# Conditioning.net
KiCad netlist of a schematic drawn in Altium Designer
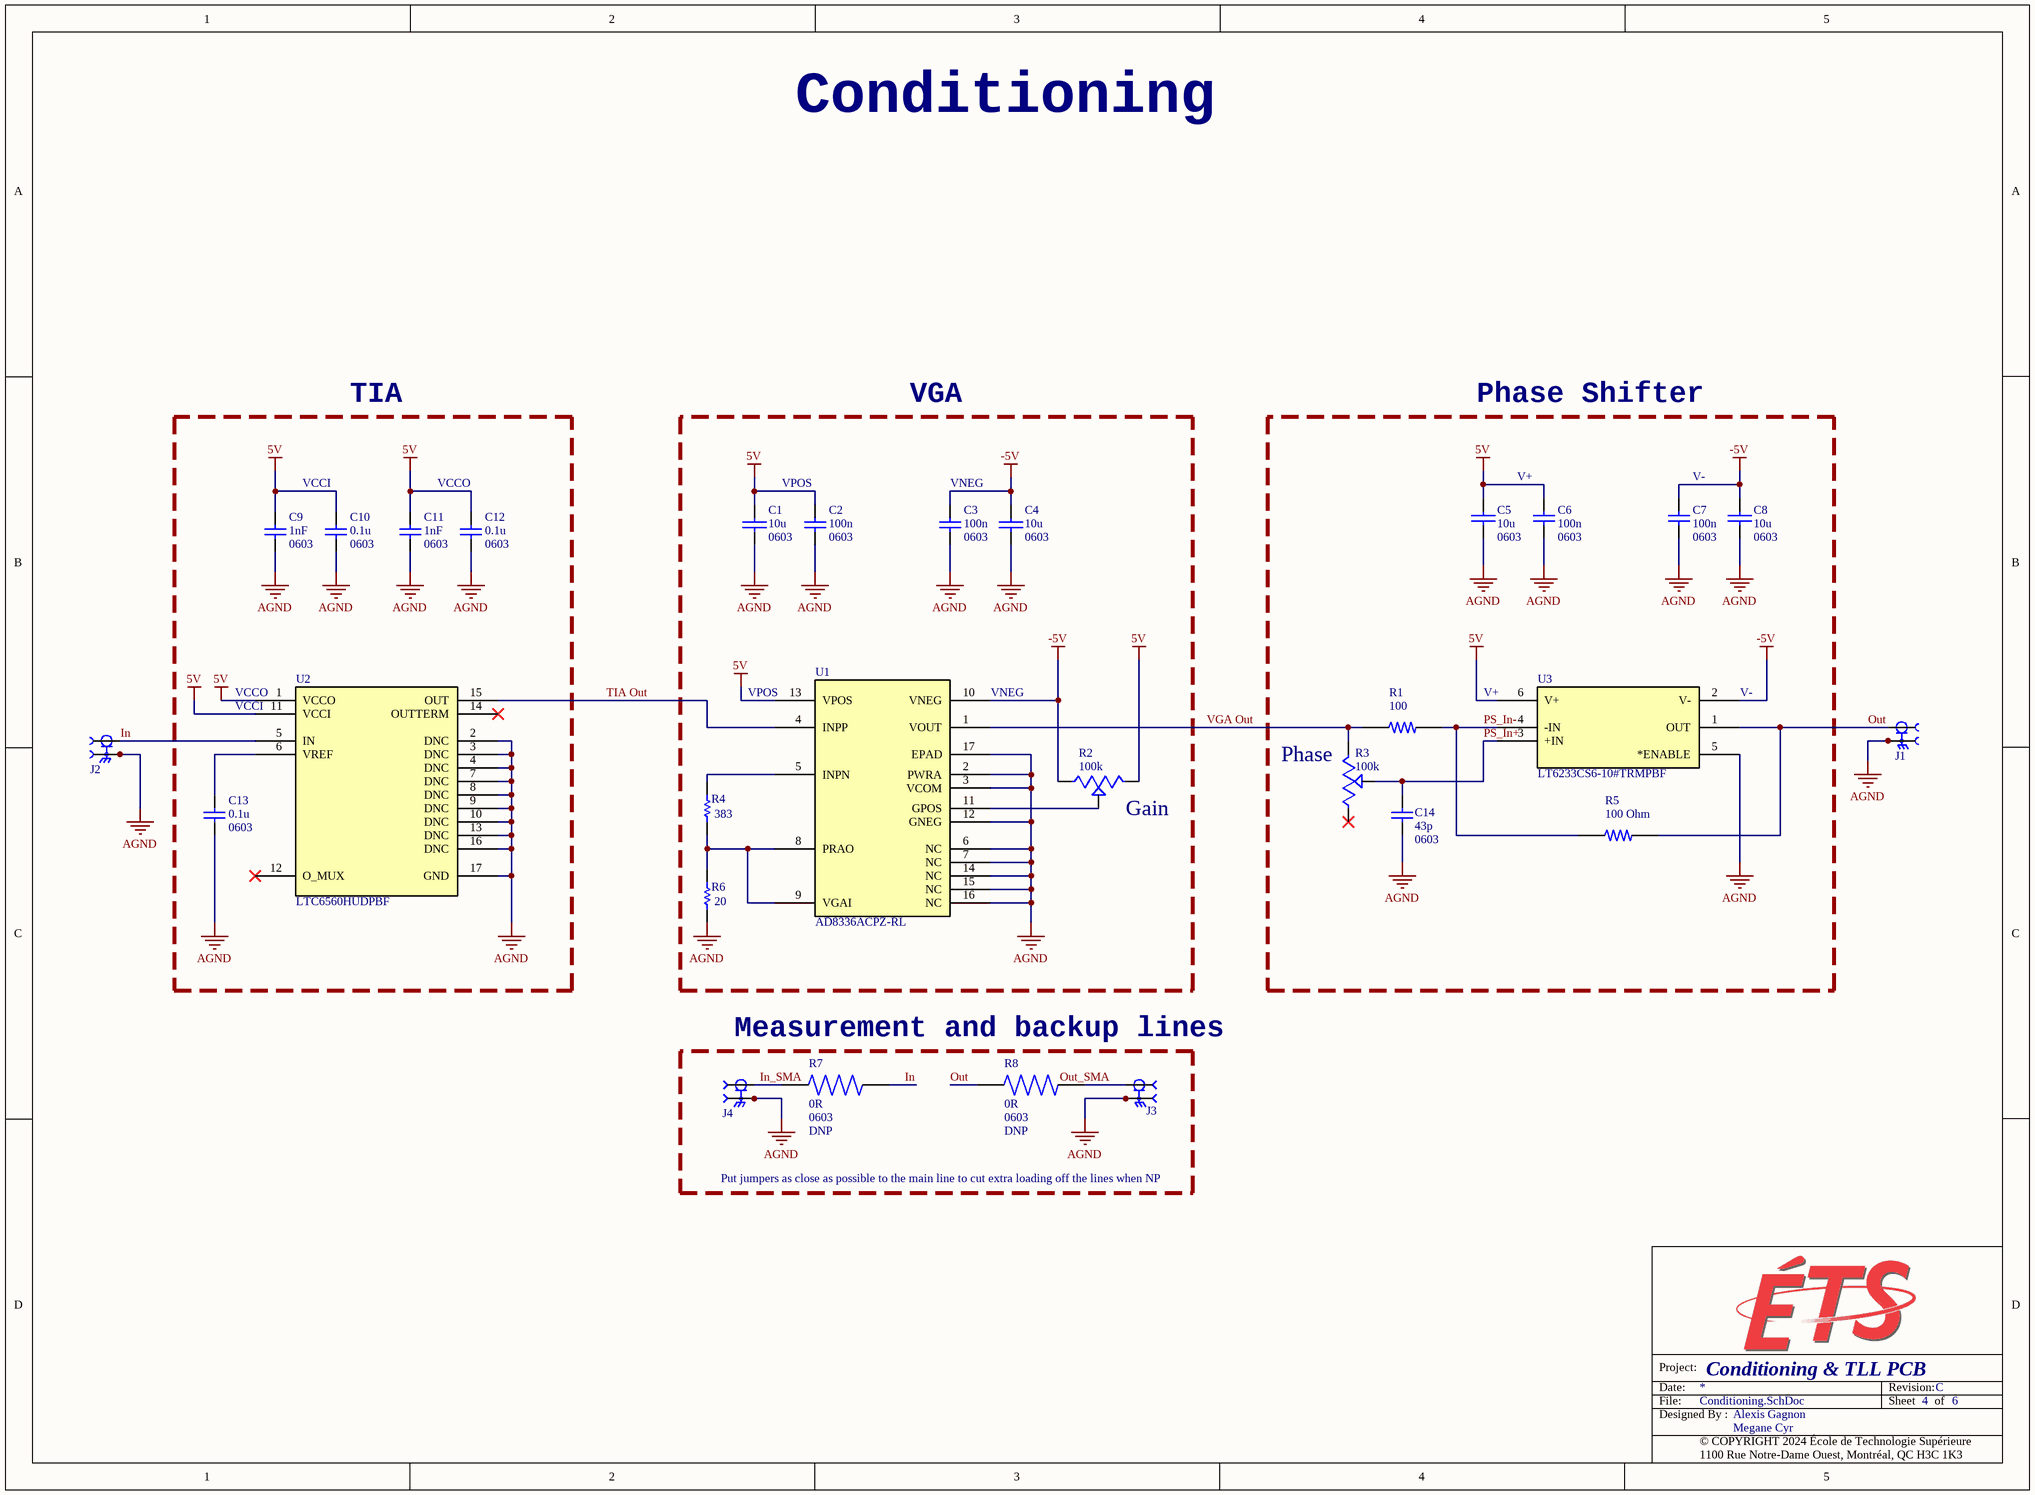
[diagram p0: Conditioning.SchDoc]

(export (version "E")
  (design (tool "Eeschema 10.0.6"))
  (components
    (comp (ref "C1")
      (value "10u")
      (footprint "C0603-V2")
      (description "CAP CER 10UF 10V X7R 0603")
      (fields
        (field (name "MANUFACTURER") "Murata")
        (field (name "MANUFACTURER PART NUMBER") "GRM188Z71A106KA73J")
        (field (name "PACKAGE") "0603")
      )
      (libsource (lib "ETS_Library") (part "GRM188Z71A106KA73J"))
    )
    (comp (ref "C2")
      (value "100n")
      (footprint "C0603-V2")
      (description "CAP CER 0.1UF 50V X7R 0603")
      (fields
        (field (name "MANUFACTURER") "Samsung")
        (field (name "MANUFACTURER PART NUMBER") "CL10B104KB8NNWC")
        (field (name "PACKAGE") "0603")
      )
      (libsource (lib "ETS_Library") (part "CL10B104KB8NNWC"))
    )
    (comp (ref "C3")
      (value "100n")
      (footprint "C0603-V2")
      (description "CAP CER 0.1UF 50V X7R 0603")
      (fields
        (field (name "MANUFACTURER") "Samsung")
        (field (name "MANUFACTURER PART NUMBER") "CL10B104KB8NNWC")
        (field (name "PACKAGE") "0603")
      )
      (libsource (lib "ETS_Library") (part "CL10B104KB8NNWC"))
    )
    (comp (ref "C4")
      (value "10u")
      (footprint "C0603-V2")
      (description "CAP CER 10UF 10V X7R 0603")
      (fields
        (field (name "MANUFACTURER") "Murata")
        (field (name "MANUFACTURER PART NUMBER") "GRM188Z71A106KA73J")
        (field (name "PACKAGE") "0603")
      )
      (libsource (lib "ETS_Library") (part "GRM188Z71A106KA73J"))
    )
    (comp (ref "C5")
      (value "10u")
      (footprint "C0603-V2")
      (description "CAP CER 10UF 10V X7R 0603")
      (fields
        (field (name "MANUFACTURER") "Murata")
        (field (name "MANUFACTURER PART NUMBER") "GRM188Z71A106KA73J")
        (field (name "PACKAGE") "0603")
      )
      (libsource (lib "ETS_Library") (part "GRM188Z71A106KA73J"))
    )
    (comp (ref "C6")
      (value "100n")
      (footprint "C0603-V2")
      (description "CAP CER 0.1UF 50V X7R 0603")
      (fields
        (field (name "MANUFACTURER") "Samsung")
        (field (name "MANUFACTURER PART NUMBER") "CL10B104KB8NNWC")
        (field (name "PACKAGE") "0603")
      )
      (libsource (lib "ETS_Library") (part "CL10B104KB8NNWC"))
    )
    (comp (ref "C7")
      (value "100n")
      (footprint "C0603-V2")
      (description "CAP CER 0.1UF 50V X7R 0603")
      (fields
        (field (name "MANUFACTURER") "Samsung")
        (field (name "MANUFACTURER PART NUMBER") "CL10B104KB8NNWC")
        (field (name "PACKAGE") "0603")
      )
      (libsource (lib "ETS_Library") (part "CL10B104KB8NNWC"))
    )
    (comp (ref "C8")
      (value "10u")
      (footprint "C0603-V2")
      (description "CAP CER 10UF 10V X7R 0603")
      (fields
        (field (name "MANUFACTURER") "Murata")
        (field (name "MANUFACTURER PART NUMBER") "GRM188Z71A106KA73J")
        (field (name "PACKAGE") "0603")
      )
      (libsource (lib "ETS_Library") (part "GRM188Z71A106KA73J"))
    )
    (comp (ref "C9")
      (value "1nF")
      (footprint "C0603-V2")
      (description "CAP CER 1000PF 50V X7R 0603")
      (fields
        (field (name "MANUFACTURER") "Samsung")
        (field (name "MANUFACTURER PART NUMBER") "CL10B102KB8NNNC")
        (field (name "PACKAGE") "0603")
      )
      (libsource (lib "ETS_Library") (part "CL10B102KB8NNNC"))
    )
    (comp (ref "C10")
      (value "0.1u")
      (footprint "C0603-V2")
      (description "CAP CER 0.1UF 50V X7R 0603")
      (fields
        (field (name "MANUFACTURER_PART_NUMBER") "CL10B104KB8NNNC")
        (field (name "PACKAGE") "0603")
        (field (name "COPYRIGHT") "Copyright (C) 2025 Ultra Librarian. All rights reserved.")
      )
      (libsource (lib "ETS_Library") (part "CL10B104KB8NNNC_1"))
    )
    (comp (ref "C11")
      (value "1nF")
      (footprint "C0603-V2")
      (description "CAP CER 1000PF 50V X7R 0603")
      (fields
        (field (name "MANUFACTURER") "Samsung")
        (field (name "MANUFACTURER PART NUMBER") "CL10B102KB8NNNC")
        (field (name "PACKAGE") "0603")
      )
      (libsource (lib "ETS_Library") (part "CL10B102KB8NNNC"))
    )
    (comp (ref "C12")
      (value "0.1u")
      (footprint "C0603-V2")
      (description "CAP CER 0.1UF 50V X7R 0603")
      (fields
        (field (name "MANUFACTURER_PART_NUMBER") "CL10B104KB8NNNC")
        (field (name "PACKAGE") "0603")
        (field (name "COPYRIGHT") "Copyright (C) 2025 Ultra Librarian. All rights reserved.")
      )
      (libsource (lib "ETS_Library") (part "CL10B104KB8NNNC_1"))
    )
    (comp (ref "C13")
      (value "0.1u")
      (footprint "CAP_CL10_SAM")
      (description "CAP CER 0.1UF 50V X7R 0603")
      (fields
        (field (name "MANUFACTURER_PART_NUMBER") "CL10B104KB8NNNC")
        (field (name "PACKAGE") "0603")
        (field (name "COPYRIGHT") "Copyright (C) 2025 Ultra Librarian. All rights reserved.")
      )
      (libsource (lib "ETS_Library") (part "CL10B104KB8NNNC_1"))
    )
    (comp (ref "C14")
      (value "43p")
      (footprint "CAPC1608X90")
      (description "CAP CER 43PF 50V C0G/NPO 0603")
      (fields (field (name "MP") "CC0603JRNPO9BN430") (field (name "PACKAGE") "0603"))
      (libsource (lib "ETS_Library") (part "CC0603JRNPO9BN430"))
    )
    (comp (ref "J1")
      (value "CONSMA001-G")
      (footprint "LINX_CONSMA001-G")
      (description "CONN SMA RCPT STR 50 OHM PCB")
      (libsource (lib "") (part "CONSMA001-G_1"))
    )
    (comp (ref "J2")
      (value "CONSMA001-G")
      (footprint "LINX_CONSMA001-G")
      (description "CONN SMA RCPT STR 50 OHM PCB")
      (libsource (lib "ETS_Library") (part "CONSMA001-G"))
    )
    (comp (ref "J3")
      (value "EMPCB.SMAFSTJ.B.HT")
      (footprint "SMA Connector")
      (description "SMA Connector Jack, Female Socket 50Ohm Board Edge, End Launch Solder")
      (fields (field (name "MF") "Taoglas Limited"))
      (libsource (lib "ELE682") (part "SMA Connector"))
    )
    (comp (ref "J4")
      (value "EMPCB.SMAFSTJ.B.HT")
      (footprint "SMA Connector")
      (description "SMA Connector Jack, Female Socket 50Ohm Board Edge, End Launch Solder")
      (fields (field (name "MF") "Taoglas Limited"))
      (libsource (lib "ELE682") (part "SMA Connector"))
    )
    (comp (ref "R1")
      (value "100")
      (footprint "RESC1607X60N")
      (description "RES SMT 100R 1% 0603 T/R PICK#92931")
      (fields (field (name "MP") "RC0603FR-07100RL"))
      (libsource (lib "ELE682") (part "RC0603FR-07100RL"))
    )
    (comp (ref "R2")
      (value "100k")
      (footprint "TRIM_3214W-1-104E")
      (description "TRIMMER 100KOHM 0.25W J LEAD TOP")
      (fields (field (name "DIGI-KEY_PART_NUMBER") "3214W-104ETR-ND") (field (name "MF") "Bourns"))
      (libsource (lib "ETS_Library") (part "3214W-1-104E"))
    )
    (comp (ref "R3")
      (value "100k")
      (footprint "TRIM_3214W-1-104E")
      (description "TRIMMER 100KOHM 0.25W J LEAD TOP")
      (fields (field (name "DIGI-KEY_PART_NUMBER") "3214W-104ETR-ND") (field (name "MF") "Bourns"))
      (libsource (lib "ETS_Library") (part "3214W-1-104E"))
    )
    (comp (ref "R4")
      (value "383")
      (footprint "RESC1608X55X25LL10T15")
      (fields (field (name "PART NUMBER") "RC0603FR-07383RL") (field (name "MANUFACTURER") "Yageo"))
      (libsource (lib "Altium Content Vault") (part "RES"))
    )
    (comp (ref "R5")
      (value "100 Ohm")
      (footprint "RESC1607X60N")
      (description "RES SMT 100R 1% 0603 T/R PICK#92931")
      (fields (field (name "MP") "RC0603FR-07100RL"))
      (libsource (lib "ELE682") (part "RC0603FR-07100RL"))
    )
    (comp (ref "R6")
      (value "20")
      (footprint "RESC1608X55X25NL10T15")
      (fields (field (name "PART NUMBER") "RC0603JR-0720RL") (field (name "MANUFACTURER") "Yageo"))
      (libsource (lib "Altium Content Vault") (part "RES"))
    )
    (comp (ref "R7")
      (value "0R")
      (footprint "RESC1508X55N")
      (description "0 Ohms Jumper 0.1W, 1/10W Chip Resistor 0603 (1608 Metric) Automotive AEC-Q200 Thick Film")
      (fields
        (field (name "PACKAGE") "0603")
        (field (name "MF") "Stackpole Electronics")
        (field (name "MP") "RMCF0603ZT0R00")
      )
      (libsource (lib "ETS_Library") (part "RMCF0603ZT0R00"))
    )
    (comp (ref "R8")
      (value "0R")
      (footprint "RESC1508X55N")
      (description "0 Ohms Jumper 0.1W, 1/10W Chip Resistor 0603 (1608 Metric) Automotive AEC-Q200 Thick Film")
      (fields
        (field (name "PACKAGE") "0603")
        (field (name "MF") "Stackpole Electronics")
        (field (name "MP") "RMCF0603ZT0R00")
      )
      (libsource (lib "ETS_Library") (part "RMCF0603ZT0R00"))
    )
    (comp (ref "U1")
      (value "AD8336ACPZ-RL")
      (footprint "CP_16_4_ADI")
      (description "General-Purpose, âˆ’55Â°C to +125Â°C, Wide Bandwidth, DC-Coupled VGA")
      (fields (field (name "COPYRIGHT") "Copyright (C) 2025 Ultra Librarian. All rights reserved."))
      (libsource (lib "ETS_Library") (part "AD8336ACPZ-RL"))
    )
    (comp (ref "U2")
      (value "LTC6560HUDPBF")
      (footprint "QFN16_UD_ADI")
      (description "No Description Available")
      (libsource (lib "ETS_Library") (part "LTC6560HUDPBF"))
    )
    (comp (ref "U3")
      (value "LT6233CS6-10#TRMPBF")
      (footprint "TSOT-23_S6_LIT")
      (description "60MHz, Rail-to-Rail Output, 1.9nV/âˆšHz, 1.2mA Op Amp Family")
      (fields (field (name "COPYRIGHT") "Copyright (C) 2025 Ultra Librarian. All rights reserved."))
      (libsource (lib "ETS_Library") (part "LT6233CS6-10TRMPBF"))
    )
  )
  (nets
    (net (code "1") (name "-5V") (class "Default")
      (node (ref "C3") (pin "2") (pinfunction "2_2") (pintype "passive"))
      (node (ref "C4") (pin "1") (pinfunction "1_1") (pintype "passive"))
      (node (ref "C7") (pin "2") (pinfunction "2_2") (pintype "passive"))
      (node (ref "C8") (pin "1") (pinfunction "1_1") (pintype "passive"))
      (node (ref "R2") (pin "1") (pinfunction "CCW_1") (pintype "passive"))
      (node (ref "U1") (pin "10") (pinfunction "VNEG_10") (pintype "passive"))
      (node (ref "U3") (pin "2") (pinfunction "V-_2") (pintype "passive"))
    )
    (net (code "2") (name "/In") (class "Default")
      (node (ref "J2") (pin "1") (pinfunction "1_1") (pintype "passive"))
      (node (ref "R7") (pin "2") (pinfunction "2_2") (pintype "passive"))
      (node (ref "U2") (pin "5") (pinfunction "IN_5") (pintype "passive"))
    )
    (net (code "3") (name "/In_SMA") (class "Default")
      (node (ref "J4") (pin "1") (pinfunction "1_1") (pintype "passive"))
      (node (ref "R7") (pin "1") (pinfunction "1_1") (pintype "passive"))
    )
    (net (code "4") (name "/Out") (class "Default")
      (node (ref "J1") (pin "1") (pinfunction "1_1") (pintype "passive"))
      (node (ref "R5") (pin "2") (pinfunction "2_2") (pintype "passive"))
      (node (ref "R8") (pin "1") (pinfunction "1_1") (pintype "passive"))
      (node (ref "U3") (pin "1") (pinfunction "OUT_1") (pintype "passive"))
    )
    (net (code "5") (name "/Out_SMA") (class "Default")
      (node (ref "J3") (pin "1") (pinfunction "1_1") (pintype "passive"))
      (node (ref "R8") (pin "2") (pinfunction "2_2") (pintype "passive"))
    )
    (net (code "6") (name "/PS_In+") (class "Default")
      (node (ref "C14") (pin "1") (pinfunction "1_1") (pintype "passive"))
      (node (ref "R3") (pin "2") (pinfunction "WIPER_2") (pintype "passive"))
      (node (ref "U3") (pin "3") (pinfunction "+IN_3") (pintype "passive"))
    )
    (net (code "7") (name "/PS_In-") (class "Default")
      (node (ref "R1") (pin "2") (pinfunction "2_2") (pintype "passive"))
      (node (ref "R5") (pin "1") (pinfunction "1_1") (pintype "passive"))
      (node (ref "U3") (pin "4") (pinfunction "-IN_4") (pintype "passive"))
    )
    (net (code "8") (name "/TIA Out") (class "Default")
      (node (ref "U1") (pin "4") (pinfunction "INPP_4") (pintype "passive"))
      (node (ref "U2") (pin "15") (pinfunction "OUT_15") (pintype "passive"))
    )
    (net (code "9") (name "/VGA Out") (class "Default")
      (node (ref "R1") (pin "1") (pinfunction "1_1") (pintype "passive"))
      (node (ref "R3") (pin "3") (pinfunction "CW_3") (pintype "passive"))
      (node (ref "U1") (pin "1") (pinfunction "VOUT_1") (pintype "passive"))
    )
    (net (code "10") (name "5V") (class "Default")
      (node (ref "C1") (pin "1") (pinfunction "1_1") (pintype "passive"))
      (node (ref "C10") (pin "2") (pinfunction "2_2") (pintype "passive"))
      (node (ref "C11") (pin "2") (pinfunction "2_2") (pintype "passive"))
      (node (ref "C12") (pin "2") (pinfunction "2_2") (pintype "passive"))
      (node (ref "C2") (pin "2") (pinfunction "2_2") (pintype "passive"))
      (node (ref "C5") (pin "1") (pinfunction "1_1") (pintype "passive"))
      (node (ref "C6") (pin "2") (pinfunction "2_2") (pintype "passive"))
      (node (ref "C9") (pin "2") (pinfunction "2_2") (pintype "passive"))
      (node (ref "R2") (pin "3") (pinfunction "CW_3") (pintype "passive"))
      (node (ref "U1") (pin "13") (pinfunction "VPOS_13") (pintype "passive"))
      (node (ref "U2") (pin "1") (pinfunction "VCCO_1") (pintype "passive"))
      (node (ref "U2") (pin "11") (pinfunction "VCCI_11") (pintype "passive"))
      (node (ref "U3") (pin "6") (pinfunction "V+_6") (pintype "passive"))
    )
    (net (code "11") (name "AGND") (class "Default")
      (node (ref "C1") (pin "2") (pinfunction "2_2") (pintype "passive"))
      (node (ref "C10") (pin "1") (pinfunction "1_1") (pintype "passive"))
      (node (ref "C11") (pin "1") (pinfunction "1_1") (pintype "passive"))
      (node (ref "C12") (pin "1") (pinfunction "1_1") (pintype "passive"))
      (node (ref "C13") (pin "1") (pinfunction "1_1") (pintype "passive"))
      (node (ref "C14") (pin "2") (pinfunction "2_2") (pintype "passive"))
      (node (ref "C2") (pin "1") (pinfunction "1_1") (pintype "passive"))
      (node (ref "C3") (pin "1") (pinfunction "1_1") (pintype "passive"))
      (node (ref "C4") (pin "2") (pinfunction "2_2") (pintype "passive"))
      (node (ref "C5") (pin "2") (pinfunction "2_2") (pintype "passive"))
      (node (ref "C6") (pin "1") (pinfunction "1_1") (pintype "passive"))
      (node (ref "C7") (pin "1") (pinfunction "1_1") (pintype "passive"))
      (node (ref "C8") (pin "2") (pinfunction "2_2") (pintype "passive"))
      (node (ref "C9") (pin "1") (pinfunction "1_1") (pintype "passive"))
      (node (ref "J1") (pin "S1") (pinfunction "2_S1") (pintype "passive"))
      (node (ref "J1") (pin "S2") (pinfunction "2_S2") (pintype "passive"))
      (node (ref "J1") (pin "S3") (pinfunction "2_S3") (pintype "passive"))
      (node (ref "J1") (pin "S4") (pinfunction "2_S4") (pintype "passive"))
      (node (ref "J2") (pin "S1") (pinfunction "2_S1") (pintype "passive"))
      (node (ref "J2") (pin "S2") (pinfunction "2_S2") (pintype "passive"))
      (node (ref "J2") (pin "S3") (pinfunction "2_S3") (pintype "passive"))
      (node (ref "J2") (pin "S4") (pinfunction "2_S4") (pintype "passive"))
      (node (ref "J3") (pin "SH1") (pinfunction "2_SH1") (pintype "passive"))
      (node (ref "J3") (pin "SH2") (pinfunction "2_SH2") (pintype "passive"))
      (node (ref "J3") (pin "SH3") (pinfunction "2_SH3") (pintype "passive"))
      (node (ref "J3") (pin "SH4") (pinfunction "2_SH4") (pintype "passive"))
      (node (ref "J4") (pin "SH1") (pinfunction "2_SH1") (pintype "passive"))
      (node (ref "J4") (pin "SH2") (pinfunction "2_SH2") (pintype "passive"))
      (node (ref "J4") (pin "SH3") (pinfunction "2_SH3") (pintype "passive"))
      (node (ref "J4") (pin "SH4") (pinfunction "2_SH4") (pintype "passive"))
      (node (ref "R6") (pin "2") (pinfunction "2_2") (pintype "passive"))
      (node (ref "U1") (pin "12") (pinfunction "GNEG_12") (pintype "passive"))
      (node (ref "U1") (pin "14") (pinfunction "NC_14") (pintype "passive"))
      (node (ref "U1") (pin "15") (pinfunction "NC_15") (pintype "passive"))
      (node (ref "U1") (pin "16") (pinfunction "NC_16") (pintype "passive"))
      (node (ref "U1") (pin "17") (pinfunction "EPAD_17") (pintype "passive"))
      (node (ref "U1") (pin "2") (pinfunction "PWRA_2") (pintype "passive"))
      (node (ref "U1") (pin "3") (pinfunction "VCOM_3") (pintype "passive"))
      (node (ref "U1") (pin "6") (pinfunction "NC_6") (pintype "passive"))
      (node (ref "U1") (pin "7") (pinfunction "NC_7") (pintype "passive"))
      (node (ref "U2") (pin "10") (pinfunction "DNC_10") (pintype "passive"))
      (node (ref "U2") (pin "13") (pinfunction "DNC_13") (pintype "passive"))
      (node (ref "U2") (pin "16") (pinfunction "DNC_16") (pintype "passive"))
      (node (ref "U2") (pin "17") (pinfunction "GND_17") (pintype "passive"))
      (node (ref "U2") (pin "2") (pinfunction "DNC_2") (pintype "passive"))
      (node (ref "U2") (pin "3") (pinfunction "DNC_3") (pintype "passive"))
      (node (ref "U2") (pin "4") (pinfunction "DNC_4") (pintype "passive"))
      (node (ref "U2") (pin "7") (pinfunction "DNC_7") (pintype "passive"))
      (node (ref "U2") (pin "8") (pinfunction "DNC_8") (pintype "passive"))
      (node (ref "U2") (pin "9") (pinfunction "DNC_9") (pintype "passive"))
      (node (ref "U3") (pin "5") (pinfunction "*ENABLE_5") (pintype "passive"))
    )
    (net (code "12") (name "Net-(R2-WIPER)") (class "Default")
      (node (ref "R2") (pin "2") (pinfunction "WIPER_2") (pintype "passive"))
      (node (ref "U1") (pin "11") (pinfunction "GPOS_11") (pintype "passive"))
    )
    (net (code "13") (name "Net-(U1-INPN)") (class "Default")
      (node (ref "R4") (pin "1") (pinfunction "1_1") (pintype "passive"))
      (node (ref "U1") (pin "5") (pinfunction "INPN_5") (pintype "passive"))
    )
    (net (code "14") (name "Net-(U1-PRAO)") (class "Default")
      (node (ref "R4") (pin "2") (pinfunction "2_2") (pintype "passive"))
      (node (ref "R6") (pin "1") (pinfunction "1_1") (pintype "passive"))
      (node (ref "U1") (pin "8") (pinfunction "PRAO_8") (pintype "passive"))
      (node (ref "U1") (pin "9") (pinfunction "VGAI_9") (pintype "passive"))
    )
    (net (code "15") (name "Net-(U2-VREF)") (class "Default")
      (node (ref "C13") (pin "2") (pinfunction "2_2") (pintype "passive"))
      (node (ref "U2") (pin "6") (pinfunction "VREF_6") (pintype "passive"))
    )
    (net (code "16") (name "unconnected-(R3-CCW-Pad1)") (class "Default")
      (node (ref "R3") (pin "1") (pinfunction "CCW_1") (pintype "passive+no_connect"))
    )
    (net (code "17") (name "unconnected-(U2-OUTTERM-Pad14)") (class "Default")
      (node (ref "U2") (pin "14") (pinfunction "OUTTERM_14") (pintype "passive+no_connect"))
    )
    (net (code "18") (name "unconnected-(U2-O_MUX-Pad12)") (class "Default")
      (node (ref "U2") (pin "12") (pinfunction "O_MUX_12") (pintype "passive+no_connect"))
    )
  )
)
